# Analog_Circuitry.net
KiCad netlist of a schematic drawn in Altium Designer
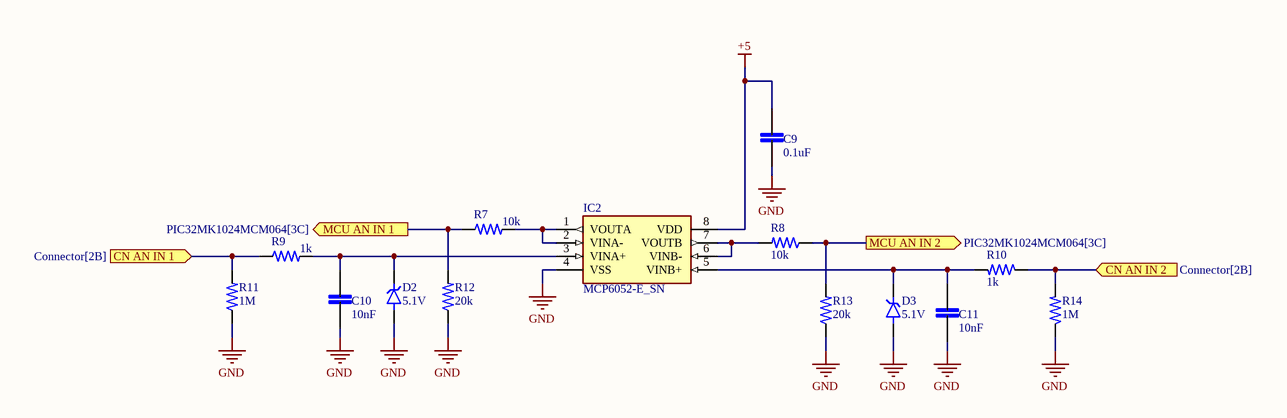
[diagram p0: Analog Circuitry.SchDoc]

(export (version "E")
  (design (tool "Eeschema 10.0.6"))
  (components
    (comp (ref "C9")
      (value "0.1uF")
      (footprint "0805")
      (fields (field (name "MP") "LD051A121KAB2A") (field (name "MF") "AVX"))
      (libsource (lib "Capacitors SMD") (part "0805_Capacitor"))
    )
    (comp (ref "C10")
      (value "10nF")
      (footprint "0805")
      (fields (field (name "MP") "LD051A121KAB2A") (field (name "MF") "AVX"))
      (libsource (lib "Capacitors SMD") (part "0805_Capacitor"))
    )
    (comp (ref "C11")
      (value "10nF")
      (footprint "0805")
      (fields (field (name "MP") "LD051A121KAB2A") (field (name "MF") "AVX"))
      (libsource (lib "") (part "0805_Capacitor_1"))
    )
    (comp (ref "D2")
      (value "5.1V")
      (footprint "SOD323")
      (fields (field (name "MP") "1SMA5926") (field (name "MF") "Taiwan Semiconductor"))
      (libsource (lib "Diodes SMD") (part "SOD323 - Zener Diode"))
    )
    (comp (ref "D3")
      (value "5.1V")
      (footprint "SOD323")
      (fields (field (name "MP") "1SMA5926") (field (name "MF") "Taiwan Semiconductor"))
      (libsource (lib "Diodes SMD") (part "SOD323 - Zener Diode"))
    )
    (comp (ref "IC2")
      (value "MCP6052-E_SN")
      (footprint "OP AMP:MCP6052-E_SN")
      (description "Integrated Circuit")
      (fields
        (field (name "MANUFACTURER_PART_NUMBER") "MCP6052-E/SN")
        (field (name "MOUSER PART NUMBER") "579-MCP6052-E/SN")
      )
      (libsource (lib "OP AMP") (part "MCP6052-E_SN"))
    )
    (comp (ref "R7")
      (value "10k")
      (footprint "0805")
      (fields
        (field (name "MP") "2-2176053-0")
        (field (name "TOLERANCE") "1%")
        (field (name "MF") "TE Connectivity")
      )
      (libsource (lib "Resistors SMD") (part "0805_Resistor"))
    )
    (comp (ref "R8")
      (value "10k")
      (footprint "0805")
      (fields
        (field (name "MP") "2-2176053-0")
        (field (name "TOLERANCE") "1%")
        (field (name "MF") "TE Connectivity")
      )
      (libsource (lib "Resistors SMD") (part "0805_Resistor"))
    )
    (comp (ref "R9")
      (value "1k")
      (footprint "0805")
      (fields
        (field (name "MP") "2-2176053-0")
        (field (name "TOLERANCE") "1%")
        (field (name "MF") "TE Connectivity")
      )
      (libsource (lib "Resistors SMD") (part "0805_Resistor"))
    )
    (comp (ref "R10")
      (value "1k")
      (footprint "0805")
      (fields
        (field (name "MP") "2-2176053-0")
        (field (name "TOLERANCE") "1%")
        (field (name "MF") "TE Connectivity")
      )
      (libsource (lib "Resistors SMD") (part "0805_Resistor"))
    )
    (comp (ref "R11")
      (value "1M")
      (footprint "0805")
      (fields
        (field (name "MP") "2-2176053-0")
        (field (name "TOLERANCE") "1%")
        (field (name "MF") "TE Connectivity")
      )
      (libsource (lib "Resistors SMD") (part "0805_Resistor"))
    )
    (comp (ref "R12")
      (value "20k")
      (footprint "0805")
      (fields
        (field (name "MP") "2-2176053-0")
        (field (name "TOLERANCE") "1%")
        (field (name "MF") "TE Connectivity")
      )
      (libsource (lib "Resistors SMD") (part "0805_Resistor"))
    )
    (comp (ref "R13")
      (value "20k")
      (footprint "0805")
      (fields
        (field (name "MP") "2-2176053-0")
        (field (name "TOLERANCE") "1%")
        (field (name "MF") "TE Connectivity")
      )
      (libsource (lib "Resistors SMD") (part "0805_Resistor"))
    )
    (comp (ref "R14")
      (value "1M")
      (footprint "0805")
      (fields
        (field (name "MP") "2-2176053-0")
        (field (name "TOLERANCE") "1%")
        (field (name "MF") "TE Connectivity")
      )
      (libsource (lib "Resistors SMD") (part "0805_Resistor"))
    )
  )
  (nets
    (net (code "1") (name "+5") (class "Default")
      (node (ref "C9") (pin "2") (pinfunction "2_2") (pintype "passive"))
      (node (ref "IC2") (pin "8") (pinfunction "VDD_8") (pintype "power_in"))
    )
    (net (code "2") (name "/CN AN IN 1") (class "Default")
      (node (ref "R11") (pin "2") (pinfunction "2_2") (pintype "passive"))
      (node (ref "R9") (pin "1") (pinfunction "1_1") (pintype "passive"))
    )
    (net (code "3") (name "/CN AN IN 2") (class "Default")
      (node (ref "R10") (pin "1") (pinfunction "1_1") (pintype "passive"))
      (node (ref "R14") (pin "2") (pinfunction "2_2") (pintype "passive"))
    )
    (net (code "4") (name "/MCU AN IN 1") (class "Default")
      (node (ref "R12") (pin "2") (pinfunction "2_2") (pintype "passive"))
      (node (ref "R7") (pin "1") (pinfunction "1_1") (pintype "passive"))
    )
    (net (code "5") (name "/MCU AN IN 2") (class "Default")
      (node (ref "R13") (pin "2") (pinfunction "2_2") (pintype "passive"))
      (node (ref "R8") (pin "1") (pinfunction "1_1") (pintype "passive"))
    )
    (net (code "6") (name "GND") (class "Default")
      (node (ref "C10") (pin "1") (pinfunction "1_1") (pintype "passive"))
      (node (ref "C11") (pin "1") (pinfunction "1_1") (pintype "passive"))
      (node (ref "C9") (pin "1") (pinfunction "1_1") (pintype "passive"))
      (node (ref "D2") (pin "2") (pinfunction "A_2") (pintype "passive"))
      (node (ref "D3") (pin "2") (pinfunction "A_2") (pintype "passive"))
      (node (ref "IC2") (pin "4") (pinfunction "VSS_4") (pintype "power_in"))
      (node (ref "R11") (pin "1") (pinfunction "1_1") (pintype "passive"))
      (node (ref "R12") (pin "1") (pinfunction "1_1") (pintype "passive"))
      (node (ref "R13") (pin "1") (pinfunction "1_1") (pintype "passive"))
      (node (ref "R14") (pin "1") (pinfunction "1_1") (pintype "passive"))
    )
    (net (code "7") (name "Net-(D2-K)") (class "Default")
      (node (ref "C10") (pin "2") (pinfunction "2_2") (pintype "passive"))
      (node (ref "D2") (pin "1") (pinfunction "K_1") (pintype "passive"))
      (node (ref "IC2") (pin "3") (pinfunction "VINA+_3") (pintype "input"))
      (node (ref "R9") (pin "2") (pinfunction "2_2") (pintype "passive"))
    )
    (net (code "8") (name "Net-(D3-K)") (class "Default")
      (node (ref "C11") (pin "2") (pinfunction "2_2") (pintype "passive"))
      (node (ref "D3") (pin "1") (pinfunction "K_1") (pintype "passive"))
      (node (ref "IC2") (pin "5") (pinfunction "VINB+_5") (pintype "input"))
      (node (ref "R10") (pin "2") (pinfunction "2_2") (pintype "passive"))
    )
    (net (code "9") (name "Net-(IC2-VINA-)") (class "Default")
      (node (ref "IC2") (pin "1") (pinfunction "VOUTA_1") (pintype "output"))
      (node (ref "IC2") (pin "2") (pinfunction "VINA-_2") (pintype "input"))
      (node (ref "R7") (pin "2") (pinfunction "2_2") (pintype "passive"))
    )
    (net (code "10") (name "Net-(IC2-VINB-)") (class "Default")
      (node (ref "IC2") (pin "6") (pinfunction "VINB-_6") (pintype "input"))
      (node (ref "IC2") (pin "7") (pinfunction "VOUTB_7") (pintype "output"))
      (node (ref "R8") (pin "2") (pinfunction "2_2") (pintype "passive"))
    )
  )
)
